# L3DCube_X16_Daughterboard.net
KiCad netlist of a schematic drawn in EAGLE
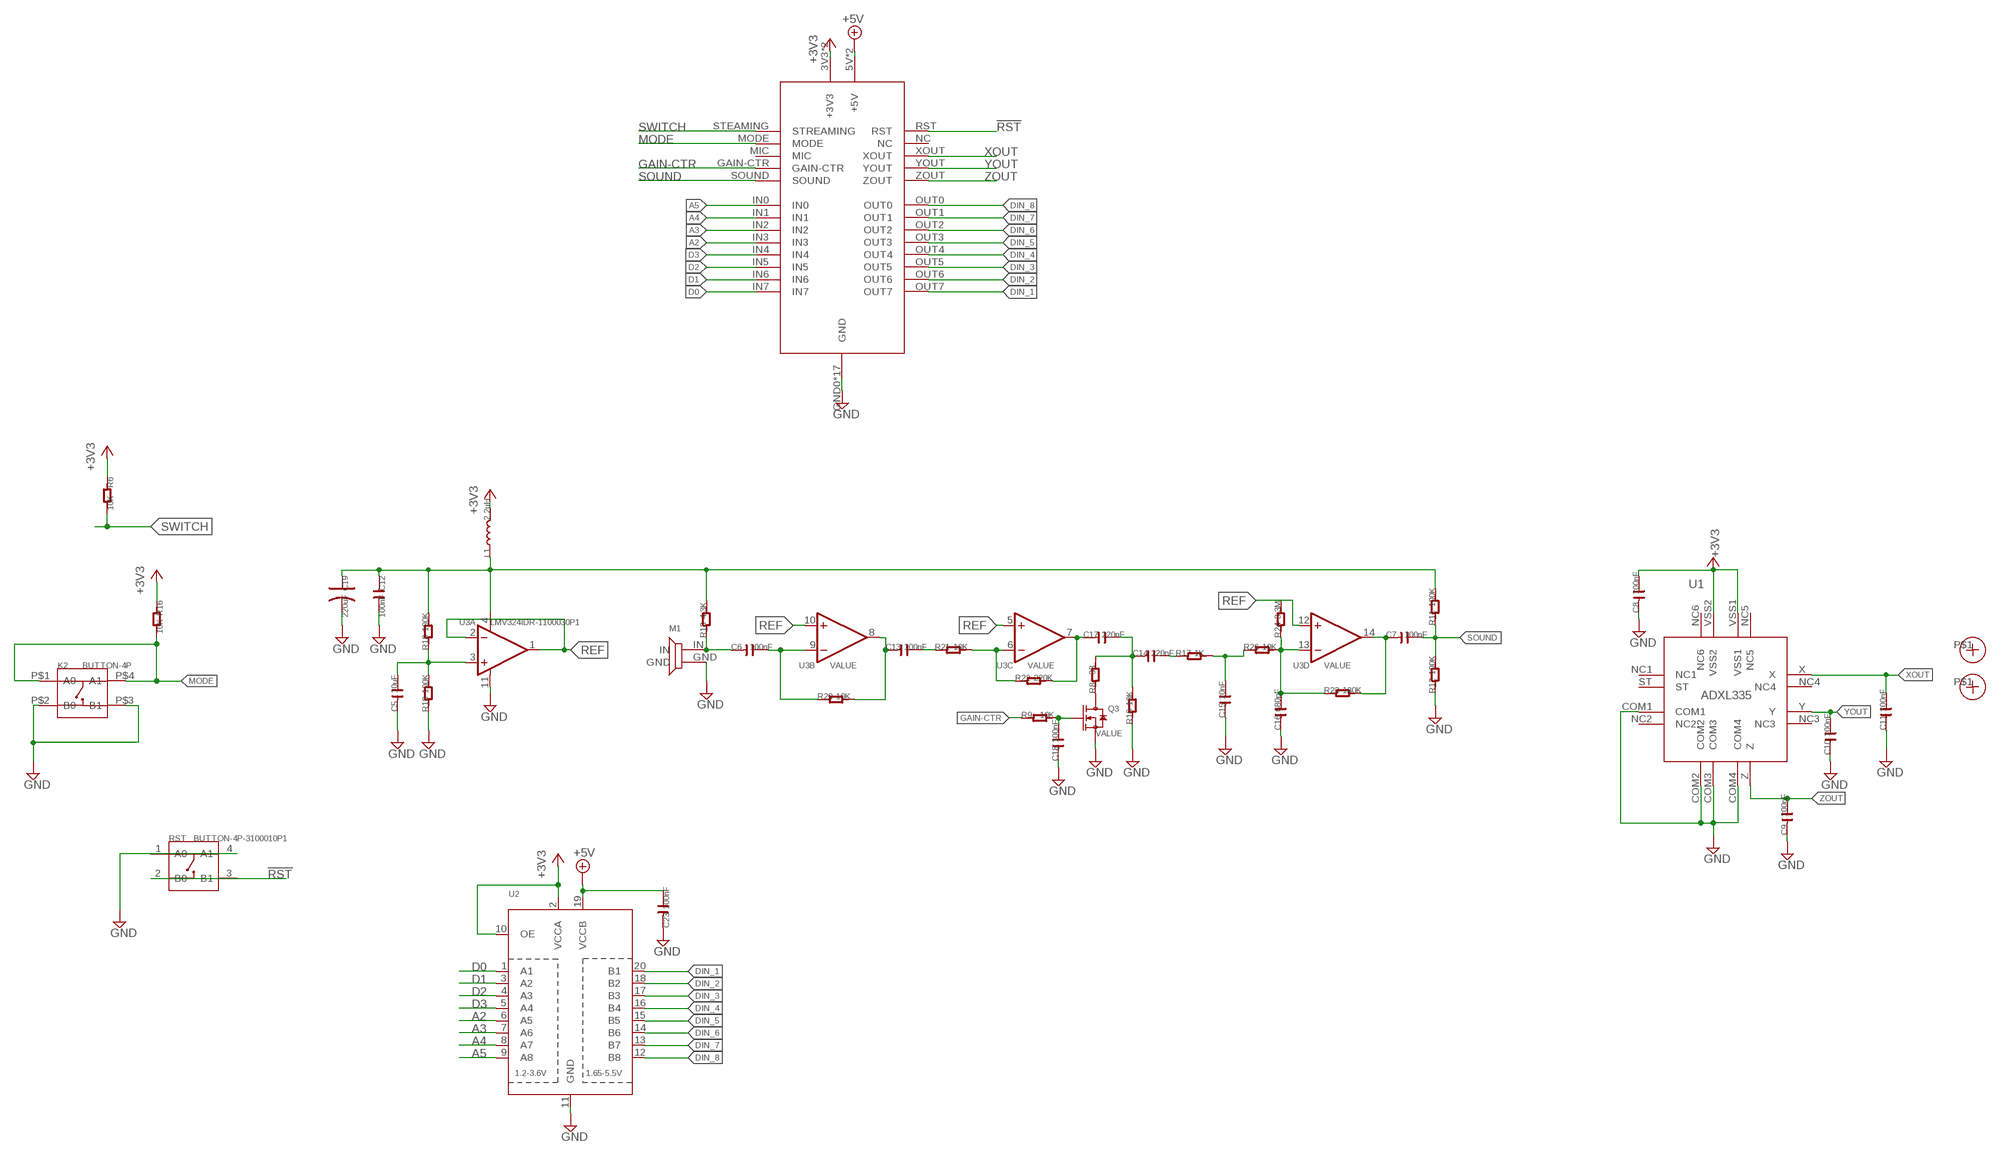
[diagram p0: schematic, sheet 1]

(export (version "E")
  (design (tool "Eeschema 10.0.6"))
  (components
    (comp (ref "C5")
      (value "10uF")
      (footprint "eagle-import:C0603")
      (libsource (lib "eagle-import") (part "C-0603"))
    )
    (comp (ref "C6")
      (value "100nF")
      (footprint "eagle-import:C0603")
      (libsource (lib "eagle-import") (part "C-0603"))
    )
    (comp (ref "C7")
      (value "100nF")
      (footprint "eagle-import:C0603")
      (libsource (lib "eagle-import") (part "C-0603"))
    )
    (comp (ref "C8")
      (value "100nF")
      (footprint "eagle-import:C0603")
      (libsource (lib "eagle-import") (part "C-0603"))
    )
    (comp (ref "C9")
      (value "100nF")
      (footprint "eagle-import:C0603")
      (libsource (lib "eagle-import") (part "C-0603"))
    )
    (comp (ref "C10")
      (value "100nF")
      (footprint "eagle-import:C0603")
      (libsource (lib "eagle-import") (part "C-0603"))
    )
    (comp (ref "C11")
      (value "100nF")
      (footprint "eagle-import:C0603")
      (libsource (lib "eagle-import") (part "C-0603"))
    )
    (comp (ref "C12")
      (value "100nF")
      (footprint "eagle-import:C0603")
      (libsource (lib "eagle-import") (part "C-0603"))
    )
    (comp (ref "C13")
      (value "100nF")
      (footprint "eagle-import:C0603")
      (libsource (lib "eagle-import") (part "C-0603"))
    )
    (comp (ref "C14")
      (value "220nF")
      (footprint "eagle-import:C0603")
      (libsource (lib "eagle-import") (part "C-0603"))
    )
    (comp (ref "C15")
      (value "10nF")
      (footprint "eagle-import:C0603")
      (libsource (lib "eagle-import") (part "C-0603"))
    )
    (comp (ref "C16")
      (value "680pF")
      (footprint "eagle-import:C0603")
      (libsource (lib "eagle-import") (part "C-0603"))
    )
    (comp (ref "C17")
      (value "220nF")
      (footprint "eagle-import:C0603")
      (libsource (lib "eagle-import") (part "C-0603"))
    )
    (comp (ref "C18")
      (value "100nF")
      (footprint "eagle-import:C0603")
      (libsource (lib "eagle-import") (part "C-0603"))
    )
    (comp (ref "C19")
      (value "220uF")
      (footprint "eagle-import:AVX-B")
      (libsource (lib "eagle-import") (part "C-POLAR-B"))
    )
    (comp (ref "C23")
      (value "100nF")
      (footprint "eagle-import:C0603")
      (libsource (lib "eagle-import") (part "C-0603"))
    )
    (comp (ref "K2")
      (value "BUTTON-4P")
      (footprint "eagle-import:4P-12X12X6-SMD")
      (libsource (lib "eagle-import") (part "BUTTON-4P"))
    )
    (comp (ref "L1")
      (value "2.2uH")
      (footprint "eagle-import:L0603")
      (libsource (lib "eagle-import") (part "L-0603"))
    )
    (comp (ref "M1")
      (value "MICROPHONE")
      (footprint "eagle-import:MICROPHONE")
      (libsource (lib "eagle-import") (part "MICROPHONE"))
    )
    (comp (ref "Q3")
      (value "2N7002")
      (footprint "eagle-import:SOT23")
      (libsource (lib "eagle-import") (part "MOSFET-N-044020001"))
    )
    (comp (ref "R6")
      (value "10K")
      (footprint "eagle-import:R0603")
      (libsource (lib "eagle-import") (part "R-0603"))
    )
    (comp (ref "R8")
      (value "33")
      (footprint "eagle-import:R0603")
      (libsource (lib "eagle-import") (part "R-0603"))
    )
    (comp (ref "R9")
      (value "10K")
      (footprint "eagle-import:R0603")
      (libsource (lib "eagle-import") (part "R-0603"))
    )
    (comp (ref "R10")
      (value "10K")
      (footprint "eagle-import:R0603")
      (libsource (lib "eagle-import") (part "R-0603"))
    )
    (comp (ref "R11")
      (value "100K")
      (footprint "eagle-import:R0603")
      (libsource (lib "eagle-import") (part "R-0603"))
    )
    (comp (ref "R12")
      (value "100K")
      (footprint "eagle-import:R0603")
      (libsource (lib "eagle-import") (part "R-0603"))
    )
    (comp (ref "R13")
      (value "4.3K")
      (footprint "eagle-import:R0603")
      (libsource (lib "eagle-import") (part "R-0603"))
    )
    (comp (ref "R16")
      (value "10K")
      (footprint "eagle-import:R0603")
      (libsource (lib "eagle-import") (part "R-0603"))
    )
    (comp (ref "R17")
      (value "1K")
      (footprint "eagle-import:R0603")
      (libsource (lib "eagle-import") (part "R-0603"))
    )
    (comp (ref "R18")
      (value "100K")
      (footprint "eagle-import:R0603")
      (libsource (lib "eagle-import") (part "R-0603"))
    )
    (comp (ref "R19")
      (value "100K")
      (footprint "eagle-import:R0603")
      (libsource (lib "eagle-import") (part "R-0603"))
    )
    (comp (ref "R20")
      (value "10K")
      (footprint "eagle-import:R0603")
      (libsource (lib "eagle-import") (part "R-0603"))
    )
    (comp (ref "R21")
      (value "10K")
      (footprint "eagle-import:R0603")
      (libsource (lib "eagle-import") (part "R-0603"))
    )
    (comp (ref "R22")
      (value "220K")
      (footprint "eagle-import:R0603")
      (libsource (lib "eagle-import") (part "R-0603"))
    )
    (comp (ref "R23")
      (value "180K")
      (footprint "eagle-import:R0603")
      (libsource (lib "eagle-import") (part "R-0603"))
    )
    (comp (ref "R24")
      (value "3.3M")
      (footprint "eagle-import:R0603")
      (libsource (lib "eagle-import") (part "R-0603"))
    )
    (comp (ref "R26")
      (value "10K")
      (footprint "eagle-import:R0603")
      (libsource (lib "eagle-import") (part "R-0603"))
    )
    (comp (ref "RST")
      (value "BUTTON-4P-3100010P1")
      (footprint "eagle-import:4P-SMD-6.0X6.0X5.0H")
      (libsource (lib "eagle-import") (part "BUTTON-4P-3100010P1"))
    )
    (comp (ref "U$1")
      (value "CUBE-16-DAUGHTERBOARD")
      (footprint "eagle-import:CUBE-16-DAUGHTERBOARD")
      (libsource (lib "eagle-import") (part "CUBE-16-DAUGHTERBOARD"))
    )
    (comp (ref "U$2")
      (value "FIDUCIAL-MARK")
      (footprint "eagle-import:FIDUCIAL-MARK")
      (libsource (lib "eagle-import") (part "FIDUCIAL-MARK"))
    )
    (comp (ref "U$3")
      (value "FIDUCIAL-MARK")
      (footprint "eagle-import:FIDUCIAL-MARK")
      (libsource (lib "eagle-import") (part "FIDUCIAL-MARK"))
    )
    (comp (ref "U1")
      (value "ADXL335")
      (footprint "eagle-import:ADXL335")
      (libsource (lib "eagle-import") (part "ADXL335"))
    )
    (comp (ref "U2")
      (value "TXB0108PWR")
      (footprint "eagle-import:TSSOP20")
      (libsource (lib "eagle-import") (part "TXB0108PWR"))
    )
    (comp (ref "U3")
      (value "LMV324IDR-1100030P1")
      (footprint "eagle-import:SOIC14")
      (libsource (lib "eagle-import") (part "LMV324IDR-1100030P1"))
    )
  )
  (nets
    (net (code "1") (name "+3V3") (class "Default")
      (node (ref "C8") (pin "2") (pinfunction "2_2") (pintype "bidirectional"))
      (node (ref "L1") (pin "2") (pinfunction "2_2") (pintype "passive"))
      (node (ref "R16") (pin "1") (pinfunction "1_1") (pintype "bidirectional"))
      (node (ref "R6") (pin "1") (pinfunction "1_1") (pintype "bidirectional"))
      (node (ref "U$1") (pin "3V3") (pinfunction "+3V3_3V3") (pintype "bidirectional"))
      (node (ref "U$1") (pin "3V3'") (pinfunction "+3V3_3V3'") (pintype "bidirectional"))
      (node (ref "U1") (pin "VSS1") (pinfunction "VSS1_VSS1") (pintype "bidirectional"))
      (node (ref "U1") (pin "VSS2") (pinfunction "VSS2_VSS2") (pintype "bidirectional"))
      (node (ref "U2") (pin "10") (pinfunction "OE_10") (pintype "bidirectional"))
      (node (ref "U2") (pin "2") (pinfunction "VCCA_2") (pintype "bidirectional"))
    )
    (net (code "2") (name "+5V") (class "Default")
      (node (ref "C23") (pin "2") (pinfunction "2_2") (pintype "bidirectional"))
      (node (ref "U$1") (pin "5V") (pinfunction "+5V_5V") (pintype "bidirectional"))
      (node (ref "U$1") (pin "5V'") (pinfunction "+5V_5V'") (pintype "bidirectional"))
      (node (ref "U2") (pin "19") (pinfunction "VCCB_19") (pintype "bidirectional"))
    )
    (net (code "3") (name "/~{RST}") (class "Default")
      (node (ref "RST") (pin "2") (pinfunction "B0_2") (pintype "bidirectional"))
      (node (ref "RST") (pin "3") (pinfunction "B1_3") (pintype "bidirectional"))
      (node (ref "U$1") (pin "RST") (pinfunction "RST_RST") (pintype "bidirectional"))
    )
    (net (code "4") (name "A2") (class "Default")
      (node (ref "U$1") (pin "IN3") (pinfunction "IN3_IN3") (pintype "bidirectional"))
      (node (ref "U2") (pin "6") (pinfunction "A5_6") (pintype "bidirectional"))
    )
    (net (code "5") (name "A3") (class "Default")
      (node (ref "U$1") (pin "IN2") (pinfunction "IN2_IN2") (pintype "bidirectional"))
      (node (ref "U2") (pin "7") (pinfunction "A6_7") (pintype "bidirectional"))
    )
    (net (code "6") (name "A4") (class "Default")
      (node (ref "U$1") (pin "IN1") (pinfunction "IN1_IN1") (pintype "bidirectional"))
      (node (ref "U2") (pin "8") (pinfunction "A7_8") (pintype "bidirectional"))
    )
    (net (code "7") (name "A5") (class "Default")
      (node (ref "U$1") (pin "IN0") (pinfunction "IN0_IN0") (pintype "bidirectional"))
      (node (ref "U2") (pin "9") (pinfunction "A8_9") (pintype "bidirectional"))
    )
    (net (code "8") (name "D0") (class "Default")
      (node (ref "U$1") (pin "IN7") (pinfunction "IN7_IN7") (pintype "bidirectional"))
      (node (ref "U2") (pin "1") (pinfunction "A1_1") (pintype "bidirectional"))
    )
    (net (code "9") (name "D1") (class "Default")
      (node (ref "U$1") (pin "IN6") (pinfunction "IN6_IN6") (pintype "bidirectional"))
      (node (ref "U2") (pin "3") (pinfunction "A2_3") (pintype "bidirectional"))
    )
    (net (code "10") (name "D2") (class "Default")
      (node (ref "U$1") (pin "IN5") (pinfunction "IN5_IN5") (pintype "bidirectional"))
      (node (ref "U2") (pin "4") (pinfunction "A3_4") (pintype "bidirectional"))
    )
    (net (code "11") (name "D3") (class "Default")
      (node (ref "U$1") (pin "IN4") (pinfunction "IN4_IN4") (pintype "bidirectional"))
      (node (ref "U2") (pin "5") (pinfunction "A4_5") (pintype "bidirectional"))
    )
    (net (code "12") (name "DIN_1") (class "Default")
      (node (ref "U$1") (pin "OUT7") (pinfunction "OUT7_OUT7") (pintype "bidirectional"))
      (node (ref "U2") (pin "20") (pinfunction "B1_20") (pintype "bidirectional"))
    )
    (net (code "13") (name "DIN_2") (class "Default")
      (node (ref "U$1") (pin "OUT6") (pinfunction "OUT6_OUT6") (pintype "bidirectional"))
      (node (ref "U2") (pin "18") (pinfunction "B2_18") (pintype "bidirectional"))
    )
    (net (code "14") (name "DIN_3") (class "Default")
      (node (ref "U$1") (pin "OUT5") (pinfunction "OUT5_OUT5") (pintype "bidirectional"))
      (node (ref "U2") (pin "17") (pinfunction "B3_17") (pintype "bidirectional"))
    )
    (net (code "15") (name "DIN_4") (class "Default")
      (node (ref "U$1") (pin "OUT4") (pinfunction "OUT4_OUT4") (pintype "bidirectional"))
      (node (ref "U2") (pin "16") (pinfunction "B4_16") (pintype "bidirectional"))
    )
    (net (code "16") (name "DIN_5") (class "Default")
      (node (ref "U$1") (pin "OUT3") (pinfunction "OUT3_OUT3") (pintype "bidirectional"))
      (node (ref "U2") (pin "15") (pinfunction "B5_15") (pintype "bidirectional"))
    )
    (net (code "17") (name "DIN_6") (class "Default")
      (node (ref "U$1") (pin "OUT2") (pinfunction "OUT2_OUT2") (pintype "bidirectional"))
      (node (ref "U2") (pin "14") (pinfunction "B6_14") (pintype "bidirectional"))
    )
    (net (code "18") (name "DIN_7") (class "Default")
      (node (ref "U$1") (pin "OUT1") (pinfunction "OUT1_OUT1") (pintype "bidirectional"))
      (node (ref "U2") (pin "13") (pinfunction "B7_13") (pintype "bidirectional"))
    )
    (net (code "19") (name "DIN_8") (class "Default")
      (node (ref "U$1") (pin "OUT0") (pinfunction "OUT0_OUT0") (pintype "bidirectional"))
      (node (ref "U2") (pin "12") (pinfunction "B8_12") (pintype "bidirectional"))
    )
    (net (code "20") (name "GAIN-CTR") (class "Default")
      (node (ref "R9") (pin "1") (pinfunction "1_1") (pintype "bidirectional"))
      (node (ref "U$1") (pin "GAIN-CTR") (pinfunction "GAIN-CTR_GAIN-CTR") (pintype "bidirectional"))
    )
    (net (code "21") (name "GND") (class "Default")
      (node (ref "C10") (pin "1") (pinfunction "1_1") (pintype "bidirectional"))
      (node (ref "C11") (pin "1") (pinfunction "1_1") (pintype "bidirectional"))
      (node (ref "C12") (pin "2") (pinfunction "2_2") (pintype "bidirectional"))
      (node (ref "C15") (pin "1") (pinfunction "1_1") (pintype "bidirectional"))
      (node (ref "C16") (pin "1") (pinfunction "1_1") (pintype "bidirectional"))
      (node (ref "C18") (pin "1") (pinfunction "1_1") (pintype "bidirectional"))
      (node (ref "C19") (pin "-") (pinfunction "2_-") (pintype "bidirectional"))
      (node (ref "C23") (pin "1") (pinfunction "1_1") (pintype "bidirectional"))
      (node (ref "C5") (pin "1") (pinfunction "1_1") (pintype "bidirectional"))
      (node (ref "C8") (pin "1") (pinfunction "1_1") (pintype "bidirectional"))
      (node (ref "C9") (pin "1") (pinfunction "1_1") (pintype "bidirectional"))
      (node (ref "K2") (pin "P$2") (pinfunction "B0_P$2") (pintype "bidirectional"))
      (node (ref "K2") (pin "P$3") (pinfunction "B1_P$3") (pintype "bidirectional"))
      (node (ref "M1") (pin "GND") (pinfunction "GND_GND") (pintype "bidirectional"))
      (node (ref "Q3") (pin "2") (pinfunction "S_2") (pintype "passive"))
      (node (ref "R10") (pin "1") (pinfunction "1_1") (pintype "bidirectional"))
      (node (ref "R12") (pin "1") (pinfunction "1_1") (pintype "bidirectional"))
      (node (ref "R19") (pin "1") (pinfunction "1_1") (pintype "bidirectional"))
      (node (ref "RST") (pin "1") (pinfunction "A0_1") (pintype "bidirectional"))
      (node (ref "RST") (pin "4") (pinfunction "A1_4") (pintype "bidirectional"))
      (node (ref "U$1") (pin "GND0") (pinfunction "GND_GND0") (pintype "bidirectional"))
      (node (ref "U$1") (pin "GND1") (pinfunction "GND_GND1") (pintype "bidirectional"))
      (node (ref "U$1") (pin "GND10") (pinfunction "GND_GND10") (pintype "bidirectional"))
      (node (ref "U$1") (pin "GND11") (pinfunction "GND_GND11") (pintype "bidirectional"))
      (node (ref "U$1") (pin "GND13") (pinfunction "GND_GND13") (pintype "bidirectional"))
      (node (ref "U$1") (pin "GND14") (pinfunction "GND_GND14") (pintype "bidirectional"))
      (node (ref "U$1") (pin "GND15") (pinfunction "GND_GND15") (pintype "bidirectional"))
      (node (ref "U$1") (pin "GND16") (pinfunction "GND_GND16") (pintype "bidirectional"))
      (node (ref "U$1") (pin "GND17") (pinfunction "GND_GND17") (pintype "bidirectional"))
      (node (ref "U$1") (pin "GND2") (pinfunction "GND_GND2") (pintype "bidirectional"))
      (node (ref "U$1") (pin "GND3") (pinfunction "GND_GND3") (pintype "bidirectional"))
      (node (ref "U$1") (pin "GND4") (pinfunction "GND_GND4") (pintype "bidirectional"))
      (node (ref "U$1") (pin "GND5") (pinfunction "GND_GND5") (pintype "bidirectional"))
      (node (ref "U$1") (pin "GND7") (pinfunction "GND_GND7") (pintype "bidirectional"))
      (node (ref "U$1") (pin "GND8") (pinfunction "GND_GND8") (pintype "bidirectional"))
      (node (ref "U$1") (pin "GND9") (pinfunction "GND_GND9") (pintype "bidirectional"))
      (node (ref "U$1") (pin "P$37") (pinfunction "GND_P$37") (pintype "bidirectional"))
      (node (ref "U1") (pin "COM1") (pinfunction "COM1_COM1") (pintype "bidirectional"))
      (node (ref "U1") (pin "COM2") (pinfunction "COM2_COM2") (pintype "bidirectional"))
      (node (ref "U1") (pin "COM3") (pinfunction "COM3_COM3") (pintype "bidirectional"))
      (node (ref "U1") (pin "COM4") (pinfunction "COM4_COM4") (pintype "bidirectional"))
      (node (ref "U2") (pin "11") (pinfunction "GND_11") (pintype "bidirectional"))
      (node (ref "U3") (pin "11") (pinfunction "V-_11") (pintype "power_in"))
    )
    (net (code "22") (name "MODE") (class "Default")
      (node (ref "K2") (pin "P$1") (pinfunction "A0_P$1") (pintype "bidirectional"))
      (node (ref "K2") (pin "P$4") (pinfunction "A1_P$4") (pintype "bidirectional"))
      (node (ref "R16") (pin "2") (pinfunction "2_2") (pintype "bidirectional"))
      (node (ref "U$1") (pin "MODE") (pinfunction "MODE_MODE") (pintype "bidirectional"))
    )
    (net (code "23") (name "Net-(C6-Pad1)") (class "Default")
      (node (ref "C6") (pin "1") (pinfunction "1_1") (pintype "bidirectional"))
      (node (ref "M1") (pin "IN") (pinfunction "IN_IN") (pintype "bidirectional"))
      (node (ref "R13") (pin "1") (pinfunction "1_1") (pintype "bidirectional"))
    )
    (net (code "24") (name "Net-(C13-Pad2)") (class "Default")
      (node (ref "C13") (pin "2") (pinfunction "2_2") (pintype "bidirectional"))
      (node (ref "R21") (pin "1") (pinfunction "1_1") (pintype "bidirectional"))
    )
    (net (code "25") (name "Net-(C14-Pad1)") (class "Default")
      (node (ref "C14") (pin "1") (pinfunction "1_1") (pintype "bidirectional"))
      (node (ref "C17") (pin "2") (pinfunction "2_2") (pintype "bidirectional"))
      (node (ref "R10") (pin "2") (pinfunction "2_2") (pintype "bidirectional"))
      (node (ref "R8") (pin "2") (pinfunction "2_2") (pintype "bidirectional"))
    )
    (net (code "26") (name "Net-(C14-Pad2)") (class "Default")
      (node (ref "C14") (pin "2") (pinfunction "2_2") (pintype "bidirectional"))
      (node (ref "R17") (pin "1") (pinfunction "1_1") (pintype "bidirectional"))
    )
    (net (code "27") (name "Net-(C15-Pad2)") (class "Default")
      (node (ref "C15") (pin "2") (pinfunction "2_2") (pintype "bidirectional"))
      (node (ref "R17") (pin "2") (pinfunction "2_2") (pintype "bidirectional"))
      (node (ref "R26") (pin "1") (pinfunction "1_1") (pintype "bidirectional"))
    )
    (net (code "28") (name "Net-(C19-1)") (class "Default")
      (node (ref "C12") (pin "1") (pinfunction "1_1") (pintype "bidirectional"))
      (node (ref "C19") (pin "+") (pinfunction "1_+") (pintype "bidirectional"))
      (node (ref "L1") (pin "1") (pinfunction "1_1") (pintype "passive"))
      (node (ref "R11") (pin "2") (pinfunction "2_2") (pintype "bidirectional"))
      (node (ref "R13") (pin "2") (pinfunction "2_2") (pintype "bidirectional"))
      (node (ref "R18") (pin "2") (pinfunction "2_2") (pintype "bidirectional"))
      (node (ref "U3") (pin "4") (pinfunction "V+_4") (pintype "power_in"))
    )
    (net (code "29") (name "Net-(Q3-D)") (class "Default")
      (node (ref "Q3") (pin "3") (pinfunction "D_3") (pintype "passive"))
      (node (ref "R8") (pin "1") (pinfunction "1_1") (pintype "bidirectional"))
    )
    (net (code "30") (name "Net-(Q3-G)") (class "Default")
      (node (ref "C18") (pin "2") (pinfunction "2_2") (pintype "bidirectional"))
      (node (ref "Q3") (pin "1") (pinfunction "G_1") (pintype "passive"))
      (node (ref "R9") (pin "2") (pinfunction "2_2") (pintype "bidirectional"))
    )
    (net (code "31") (name "Net-(U3A-IN+)") (class "Default")
      (node (ref "C5") (pin "2") (pinfunction "2_2") (pintype "bidirectional"))
      (node (ref "R18") (pin "1") (pinfunction "1_1") (pintype "bidirectional"))
      (node (ref "R19") (pin "2") (pinfunction "2_2") (pintype "bidirectional"))
      (node (ref "U3") (pin "3") (pinfunction "IN+_3") (pintype "input"))
    )
    (net (code "32") (name "Net-(U3B-IN-)") (class "Default")
      (node (ref "C6") (pin "2") (pinfunction "2_2") (pintype "bidirectional"))
      (node (ref "R20") (pin "1") (pinfunction "1_1") (pintype "bidirectional"))
      (node (ref "U3") (pin "9") (pinfunction "IN-_9") (pintype "input"))
    )
    (net (code "33") (name "Net-(U3B-OUT)") (class "Default")
      (node (ref "C13") (pin "1") (pinfunction "1_1") (pintype "bidirectional"))
      (node (ref "R20") (pin "2") (pinfunction "2_2") (pintype "bidirectional"))
      (node (ref "U3") (pin "8") (pinfunction "OUT_8") (pintype "output"))
    )
    (net (code "34") (name "Net-(U3C-IN-)") (class "Default")
      (node (ref "R21") (pin "2") (pinfunction "2_2") (pintype "bidirectional"))
      (node (ref "R22") (pin "1") (pinfunction "1_1") (pintype "bidirectional"))
      (node (ref "U3") (pin "6") (pinfunction "IN-_6") (pintype "input"))
    )
    (net (code "35") (name "Net-(U3C-OUT)") (class "Default")
      (node (ref "C17") (pin "1") (pinfunction "1_1") (pintype "bidirectional"))
      (node (ref "R22") (pin "2") (pinfunction "2_2") (pintype "bidirectional"))
      (node (ref "U3") (pin "7") (pinfunction "OUT_7") (pintype "output"))
    )
    (net (code "36") (name "Net-(U3D-IN-)") (class "Default")
      (node (ref "C16") (pin "2") (pinfunction "2_2") (pintype "bidirectional"))
      (node (ref "R23") (pin "1") (pinfunction "1_1") (pintype "bidirectional"))
      (node (ref "R24") (pin "1") (pinfunction "1_1") (pintype "bidirectional"))
      (node (ref "R26") (pin "2") (pinfunction "2_2") (pintype "bidirectional"))
      (node (ref "U3") (pin "13") (pinfunction "IN-_13") (pintype "input"))
    )
    (net (code "37") (name "Net-(U3D-OUT)") (class "Default")
      (node (ref "C7") (pin "1") (pinfunction "1_1") (pintype "bidirectional"))
      (node (ref "R23") (pin "2") (pinfunction "2_2") (pintype "bidirectional"))
      (node (ref "U3") (pin "14") (pinfunction "OUT_14") (pintype "output"))
    )
    (net (code "38") (name "REF") (class "Default")
      (node (ref "R24") (pin "2") (pinfunction "2_2") (pintype "bidirectional"))
      (node (ref "U3") (pin "1") (pinfunction "OUT_1") (pintype "output"))
      (node (ref "U3") (pin "10") (pinfunction "IN+_10") (pintype "input"))
      (node (ref "U3") (pin "12") (pinfunction "IN+_12") (pintype "input"))
      (node (ref "U3") (pin "2") (pinfunction "IN-_2") (pintype "input"))
      (node (ref "U3") (pin "5") (pinfunction "IN+_5") (pintype "input"))
    )
    (net (code "39") (name "SOUND") (class "Default")
      (node (ref "C7") (pin "2") (pinfunction "2_2") (pintype "bidirectional"))
      (node (ref "R11") (pin "1") (pinfunction "1_1") (pintype "bidirectional"))
      (node (ref "R12") (pin "2") (pinfunction "2_2") (pintype "bidirectional"))
      (node (ref "U$1") (pin "SOUND") (pinfunction "SOUND_SOUND") (pintype "bidirectional"))
    )
    (net (code "40") (name "SWITCH") (class "Default")
      (node (ref "R6") (pin "2") (pinfunction "2_2") (pintype "bidirectional"))
      (node (ref "U$1") (pin "STEAMING") (pinfunction "STREAMING_STEAMING") (pintype "bidirectional"))
    )
    (net (code "41") (name "XOUT") (class "Default")
      (node (ref "C11") (pin "2") (pinfunction "2_2") (pintype "bidirectional"))
      (node (ref "U$1") (pin "XOUT") (pinfunction "XOUT_XOUT") (pintype "bidirectional"))
      (node (ref "U1") (pin "X") (pinfunction "X_X") (pintype "bidirectional"))
    )
    (net (code "42") (name "YOUT") (class "Default")
      (node (ref "C10") (pin "2") (pinfunction "2_2") (pintype "bidirectional"))
      (node (ref "U$1") (pin "YOUT") (pinfunction "YOUT_YOUT") (pintype "bidirectional"))
      (node (ref "U1") (pin "Y") (pinfunction "Y_Y") (pintype "bidirectional"))
    )
    (net (code "43") (name "ZOUT") (class "Default")
      (node (ref "C9") (pin "2") (pinfunction "2_2") (pintype "bidirectional"))
      (node (ref "U$1") (pin "ZOUT") (pinfunction "ZOUT_ZOUT") (pintype "bidirectional"))
      (node (ref "U1") (pin "Z") (pinfunction "Z_Z") (pintype "bidirectional"))
    )
    (net (code "44") (name "unconnected-(U$1-PadMIC)") (class "Default")
      (node (ref "U$1") (pin "MIC") (pinfunction "MIC_MIC") (pintype "bidirectional"))
    )
    (net (code "45") (name "unconnected-(U$1-PadNC)") (class "Default")
      (node (ref "U$1") (pin "NC") (pinfunction "NC_NC") (pintype "bidirectional"))
    )
    (net (code "46") (name "unconnected-(U$2-PadP$1)") (class "Default")
      (node (ref "U$2") (pin "P$1") (pinfunction "P$1_P$1") (pintype "bidirectional"))
    )
    (net (code "47") (name "unconnected-(U$3-PadP$1)") (class "Default")
      (node (ref "U$3") (pin "P$1") (pinfunction "P$1_P$1") (pintype "bidirectional"))
    )
    (net (code "48") (name "unconnected-(U1-PadNC1)") (class "Default")
      (node (ref "U1") (pin "NC1") (pinfunction "NC1_NC1") (pintype "bidirectional"))
    )
    (net (code "49") (name "unconnected-(U1-PadNC2)") (class "Default")
      (node (ref "U1") (pin "NC2") (pinfunction "NC2_NC2") (pintype "bidirectional"))
    )
    (net (code "50") (name "unconnected-(U1-PadNC3)") (class "Default")
      (node (ref "U1") (pin "NC3") (pinfunction "NC3_NC3") (pintype "bidirectional"))
    )
    (net (code "51") (name "unconnected-(U1-PadNC4)") (class "Default")
      (node (ref "U1") (pin "NC4") (pinfunction "NC4_NC4") (pintype "bidirectional"))
    )
    (net (code "52") (name "unconnected-(U1-PadNC5)") (class "Default")
      (node (ref "U1") (pin "NC5") (pinfunction "NC5_NC5") (pintype "bidirectional"))
    )
    (net (code "53") (name "unconnected-(U1-PadNC6)") (class "Default")
      (node (ref "U1") (pin "NC6") (pinfunction "NC6_NC6") (pintype "bidirectional"))
    )
    (net (code "54") (name "unconnected-(U1-PadST)") (class "Default")
      (node (ref "U1") (pin "ST") (pinfunction "ST_ST") (pintype "bidirectional"))
    )
  )
)
